# relays.net
KiCad netlist of a schematic drawn in Altium Designer
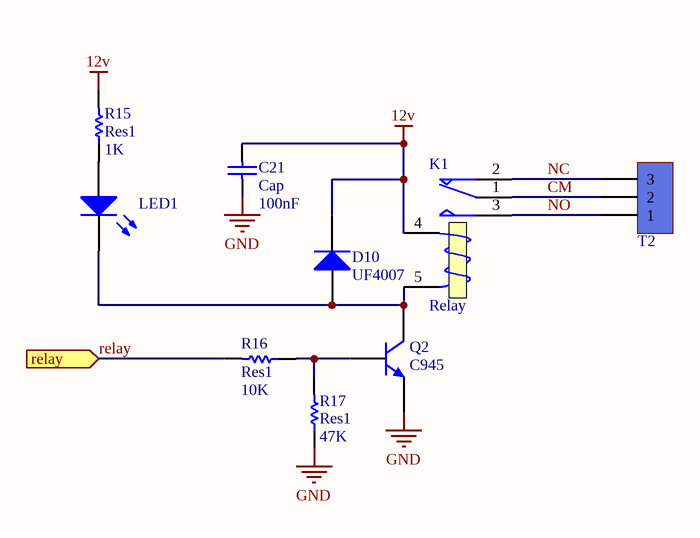
[diagram p0: relays.SchDoc]

(export (version "E")
  (design (tool "Eeschema 10.0.6"))
  (components
    (comp (ref "C21")
      (value "Cap")
      (footprint "CAP 1206 (3216X15L)")
      (description "CAP-100Nf")
      (fields (field (name "ALTIUM_VALUE") "100nF"))
      (libsource (lib "Altium library (www.AVRelec.com)") (part "Cap ceramic"))
    )
    (comp (ref "D10")
      (value "UF4007")
      (footprint "SMA DIODE 2")
      (description "Default Diode")
      (fields (field (name "PUBLISHER") "Altium Limited"))
      (libsource (lib "Miscellaneous Devices") (part "Diode"))
    )
    (comp (ref "K1")
      (value "Relay")
      (footprint "Relay 15.40x12.10x13.10")
      (description "Relay_SPDT POWER NEEDLE")
      (fields (field (name "DESIGNER") "Ali Hafizi"))
      (libsource (lib "Altium (2)") (part "RELAY General"))
    )
    (comp (ref "LED1")
      (value "LED0")
      (footprint "LED 1206")
      (description "Typical INFRARED GaAs LED")
      (fields (field (name "PUBLISHER") "Altium Limited"))
      (libsource (lib "Miscellaneous Devices") (part "LED0"))
    )
    (comp (ref "Q2")
      (value "C945")
      (footprint "SOT23_N")
      (description "NPN Silicon Epitaxial Planar Transistor")
      (fields (field (name "PUBLISHER") "Abbas Basereh"))
      (libsource (lib "Altium (2)") (part "C945"))
    )
    (comp (ref "R15")
      (value "Res1")
      (footprint "RES 1206 (3216X08L)")
      (description "Resistor")
      (fields (field (name "ALTIUM_VALUE") "1K") (field (name "PUBLISHER") "Altium Limited"))
      (libsource (lib "Miscellaneous Devices") (part "Res1"))
    )
    (comp (ref "R16")
      (value "Res1")
      (footprint "RES 1206 (3216X08L)")
      (description "Resistor")
      (fields (field (name "ALTIUM_VALUE") "10K") (field (name "PUBLISHER") "Altium Limited"))
      (libsource (lib "Miscellaneous Devices") (part "Res1"))
    )
    (comp (ref "R17")
      (value "Res1")
      (footprint "RES 1206 (3216X08L)")
      (description "Resistor")
      (fields (field (name "ALTIUM_VALUE") "47K") (field (name "PUBLISHER") "Altium Limited"))
      (libsource (lib "Miscellaneous Devices") (part "Res1"))
    )
    (comp (ref "T2")
      (value "Terminal")
      (footprint "Terminal 1*3")
      (description "Terminal 3 Pin 250VAC 16A")
      (fields (field (name "DESIGNER") "Seyed Mohsen Ghasemain") (field (name "E-MAIL") "picpars@gmail.com"))
      (libsource (lib "PicPars.com_usefully_Library") (part "Terminal 1*3"))
    )
  )
  (nets
    (net (code "1") (name "/CM") (class "Default")
      (node (ref "K1") (pin "1") (pinfunction "COM_1") (pintype "passive"))
      (node (ref "T2") (pin "2") (pinfunction "2_2") (pintype "passive"))
    )
    (net (code "2") (name "/NC") (class "Default")
      (node (ref "K1") (pin "2") (pinfunction "NC_2") (pintype "passive"))
      (node (ref "T2") (pin "3") (pinfunction "3_3") (pintype "passive"))
    )
    (net (code "3") (name "/NO") (class "Default")
      (node (ref "K1") (pin "3") (pinfunction "NO_3") (pintype "passive"))
      (node (ref "T2") (pin "1") (pinfunction "1_1") (pintype "passive"))
    )
    (net (code "4") (name "/relay") (class "Default")
      (node (ref "R16") (pin "2") (pinfunction "2_2") (pintype "passive"))
    )
    (net (code "5") (name "12v") (class "Default")
      (node (ref "C21") (pin "2") (pinfunction "2_2") (pintype "passive"))
      (node (ref "D10") (pin "2") (pinfunction "K_2") (pintype "passive"))
      (node (ref "K1") (pin "4") (pinfunction "T1_4") (pintype "passive"))
      (node (ref "R15") (pin "2") (pinfunction "2_2") (pintype "passive"))
    )
    (net (code "6") (name "GND") (class "Default")
      (node (ref "C21") (pin "1") (pinfunction "1_1") (pintype "passive"))
      (node (ref "Q2") (pin "2") (pinfunction "E_2") (pintype "passive"))
      (node (ref "R17") (pin "1") (pinfunction "1_1") (pintype "passive"))
    )
    (net (code "7") (name "Net-(D10-A)") (class "Default")
      (node (ref "D10") (pin "1") (pinfunction "A_1") (pintype "passive"))
      (node (ref "K1") (pin "5") (pinfunction "T2_5") (pintype "passive"))
      (node (ref "LED1") (pin "2") (pinfunction "K_2") (pintype "passive"))
      (node (ref "Q2") (pin "3") (pinfunction "C_3") (pintype "passive"))
    )
    (net (code "8") (name "Net-(LED1-A)") (class "Default")
      (node (ref "LED1") (pin "1") (pinfunction "A_1") (pintype "passive"))
      (node (ref "R15") (pin "1") (pinfunction "1_1") (pintype "passive"))
    )
    (net (code "9") (name "Net-(Q2-B)") (class "Default")
      (node (ref "Q2") (pin "1") (pinfunction "B_1") (pintype "passive"))
      (node (ref "R16") (pin "1") (pinfunction "1_1") (pintype "passive"))
      (node (ref "R17") (pin "2") (pinfunction "2_2") (pintype "passive"))
    )
  )
)
